# BPW5002-microSD_1_3.net
KiCad netlist of a schematic drawn in EAGLE
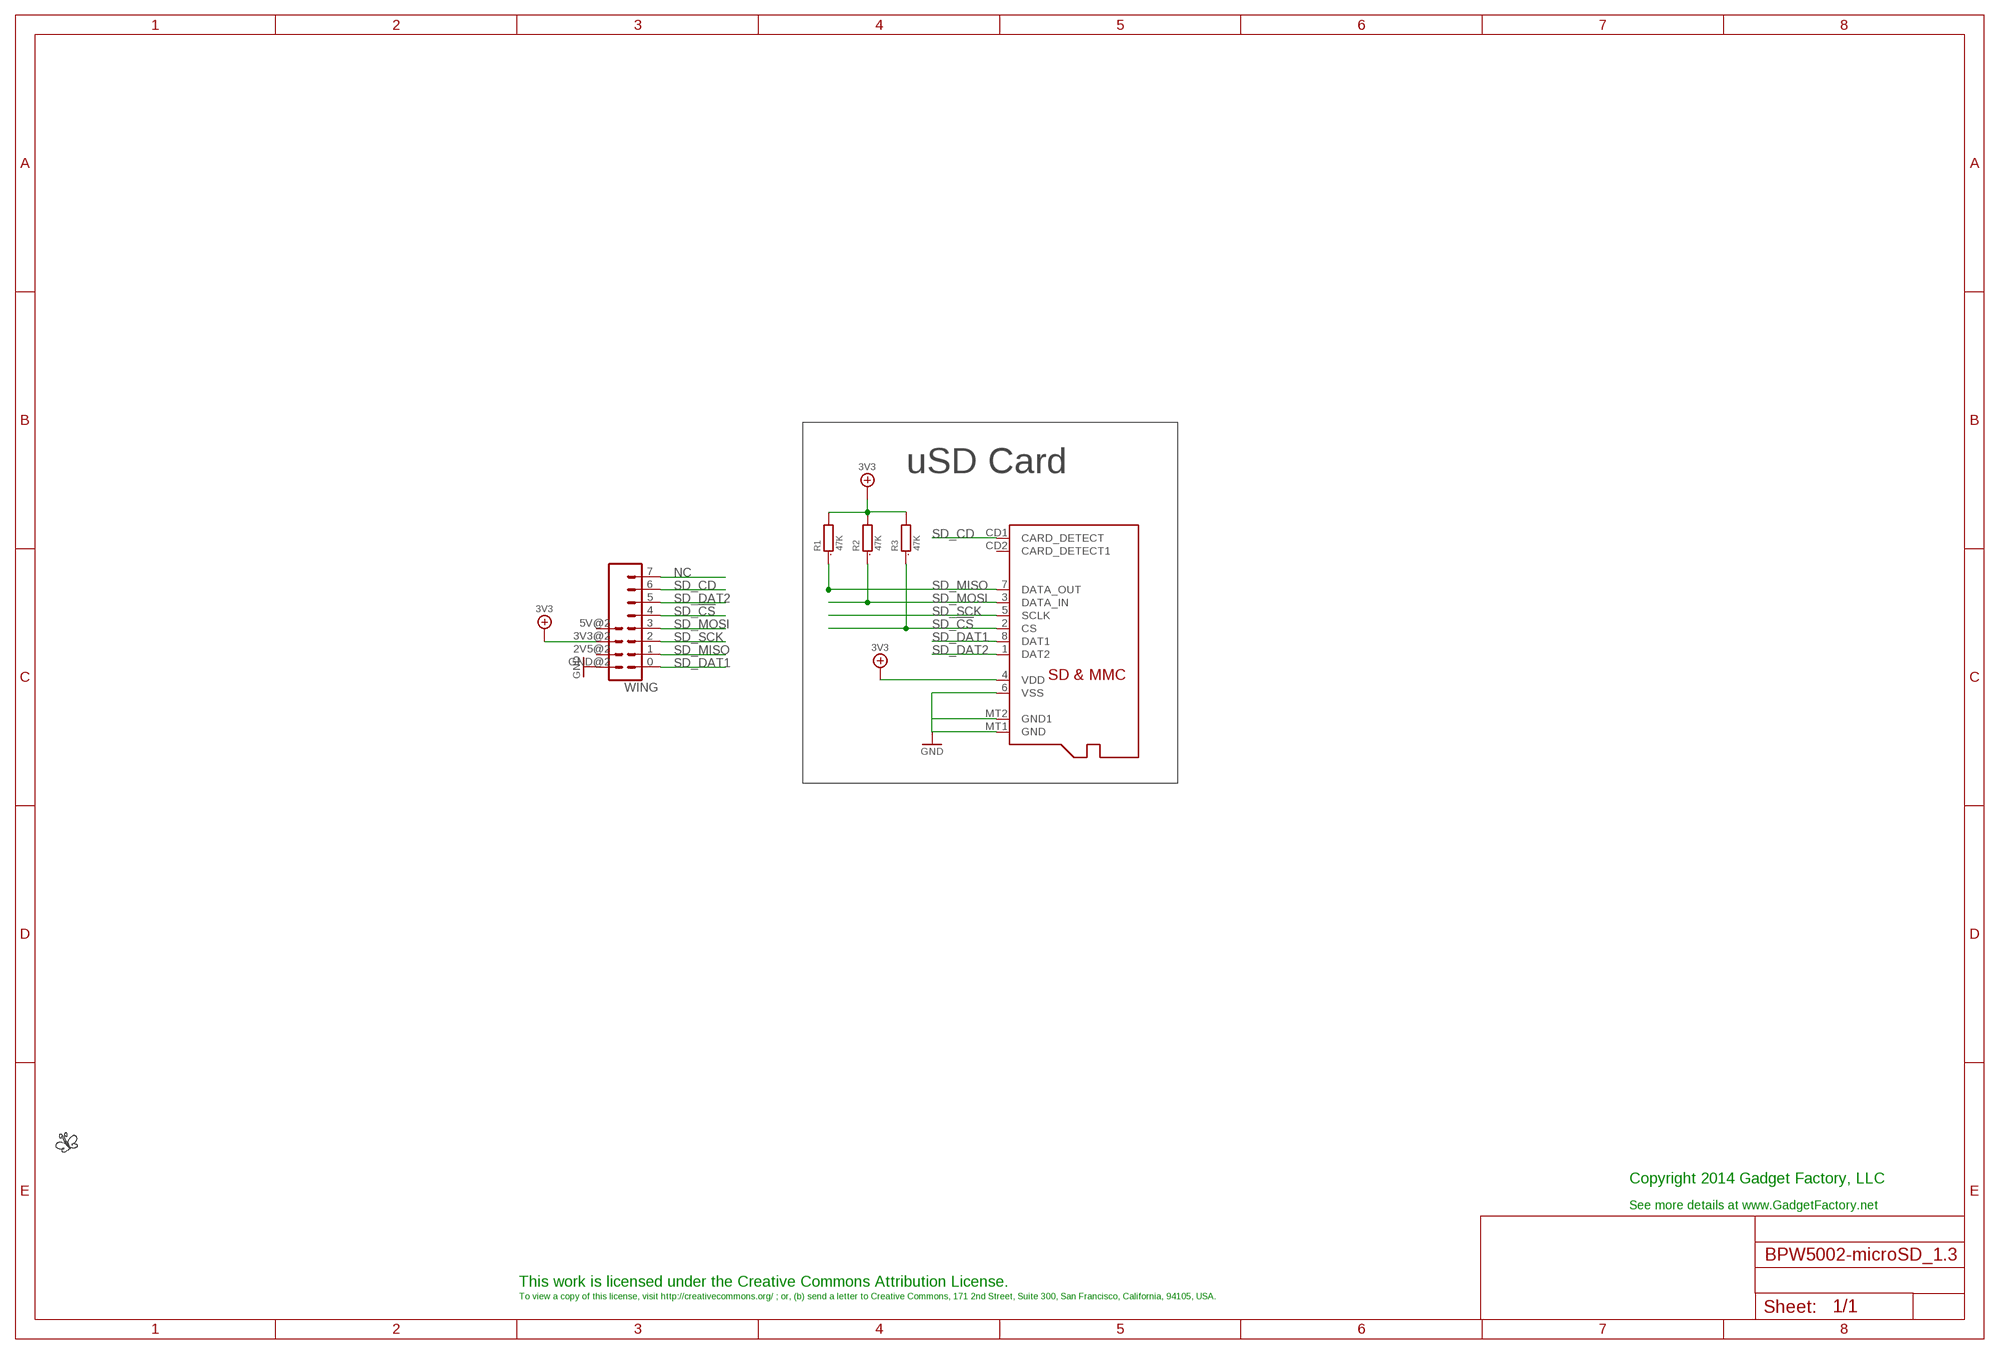
[diagram p0: schematic, sheet 1]

(export (version "E")
  (design (tool "Eeschema 10.0.6"))
  (components
    (comp (ref "LOGO2")
      (value "BUTTERFLY_LOGO")
      (footprint "eagle-import:BUTTERFLY_LOGO")
      (libsource (lib "eagle-import") (part "BUTTERFLY_LOGO"))
    )
    (comp (ref "R1")
      (value "47K")
      (footprint "eagle-import:0805")
      (fields (field (name "PARTNO") "RMCF0805JT47K0"))
      (libsource (lib "eagle-import") (part "R0805"))
    )
    (comp (ref "R2")
      (value "47K")
      (footprint "eagle-import:0805")
      (fields (field (name "PARTNO") "RMCF0805JT47K0"))
      (libsource (lib "eagle-import") (part "R0805"))
    )
    (comp (ref "R3")
      (value "47K")
      (footprint "eagle-import:0805")
      (fields (field (name "PARTNO") "RMCF0805JT47K0"))
      (libsource (lib "eagle-import") (part "R0805"))
    )
    (comp (ref "SD1")
      (value "MICROSD")
      (footprint "eagle-import:MICROSD")
      (fields (field (name "PARTNO") "101-00660-68-6"))
      (libsource (lib "eagle-import") (part "MICROSD"))
    )
    (comp (ref "WING")
      (value "WING8WING8_NOHOLES")
      (footprint "eagle-import:WINGSIDE_8BIT_NOHOLES")
      (fields (field (name "PARTNO") "68001-112HLF"))
      (libsource (lib "eagle-import") (part "WING8WING8_NOHOLES"))
    )
  )
  (nets
    (net (code "1") (name "/NC") (class "Default")
      (node (ref "WING") (pin "7") (pinfunction "8_7") (pintype "passive"))
    )
    (net (code "2") (name "/SD_CD") (class "Default")
      (node (ref "SD1") (pin "CD1") (pinfunction "CARD_DETECT_CD1") (pintype "passive"))
      (node (ref "WING") (pin "6") (pinfunction "7_6") (pintype "passive"))
    )
    (net (code "3") (name "/SD_DAT1") (class "Default")
      (node (ref "SD1") (pin "8") (pinfunction "DAT1_8") (pintype "bidirectional"))
      (node (ref "WING") (pin "0") (pinfunction "1_0") (pintype "passive"))
    )
    (net (code "4") (name "/SD_DAT2") (class "Default")
      (node (ref "SD1") (pin "1") (pinfunction "DAT2_1") (pintype "bidirectional"))
      (node (ref "WING") (pin "5") (pinfunction "6_5") (pintype "passive"))
    )
    (net (code "5") (name "/SD_MISO") (class "Default")
      (node (ref "R1") (pin "1") (pinfunction "1_1") (pintype "passive"))
      (node (ref "SD1") (pin "7") (pinfunction "DATA_OUT_7") (pintype "output"))
      (node (ref "WING") (pin "1") (pinfunction "2_1") (pintype "passive"))
    )
    (net (code "6") (name "/SD_MOSI") (class "Default")
      (node (ref "R2") (pin "1") (pinfunction "1_1") (pintype "passive"))
      (node (ref "SD1") (pin "3") (pinfunction "DATA_IN_3") (pintype "input"))
      (node (ref "WING") (pin "3") (pinfunction "4_3") (pintype "passive"))
    )
    (net (code "7") (name "/SD_SCK") (class "Default")
      (node (ref "SD1") (pin "5") (pinfunction "SCLK_5") (pintype "input"))
      (node (ref "WING") (pin "2") (pinfunction "3_2") (pintype "passive"))
    )
    (net (code "8") (name "/SD_~{CS}") (class "Default")
      (node (ref "R3") (pin "1") (pinfunction "1_1") (pintype "passive"))
      (node (ref "SD1") (pin "2") (pinfunction "CS_2") (pintype "input"))
      (node (ref "WING") (pin "4") (pinfunction "5_4") (pintype "passive"))
    )
    (net (code "9") (name "3V3") (class "Default")
      (node (ref "R1") (pin "2") (pinfunction "2_2") (pintype "passive"))
      (node (ref "R2") (pin "2") (pinfunction "2_2") (pintype "passive"))
      (node (ref "R3") (pin "2") (pinfunction "2_2") (pintype "passive"))
      (node (ref "SD1") (pin "4") (pinfunction "VDD_4") (pintype "power_in"))
      (node (ref "WING") (pin "3V3@2") (pinfunction "3V3_3V3@2") (pintype "passive"))
    )
    (net (code "10") (name "GND") (class "Default")
      (node (ref "SD1") (pin "6") (pinfunction "VSS_6") (pintype "power_in"))
      (node (ref "SD1") (pin "MT1") (pinfunction "GND_MT1") (pintype "power_in"))
      (node (ref "SD1") (pin "MT2") (pinfunction "GND1_MT2") (pintype "power_in"))
      (node (ref "WING") (pin "GND@2") (pinfunction "GND_GND@2") (pintype "passive"))
    )
    (net (code "11") (name "unconnected-(SD1-CARD_DETECT1-PadCD2)") (class "Default")
      (node (ref "SD1") (pin "CD2") (pinfunction "CARD_DETECT1_CD2") (pintype "passive"))
    )
    (net (code "12") (name "unconnected-(WING-2V5-Pad2V5@2)") (class "Default")
      (node (ref "WING") (pin "2V5@2") (pinfunction "2V5_2V5@2") (pintype "passive"))
    )
    (net (code "13") (name "unconnected-(WING-5V-Pad5V@2)") (class "Default")
      (node (ref "WING") (pin "5V@2") (pinfunction "5V_5V@2") (pintype "passive"))
    )
  )
)
